# SCH_Power_Jack.net
KiCad netlist of a schematic drawn in Altium Designer
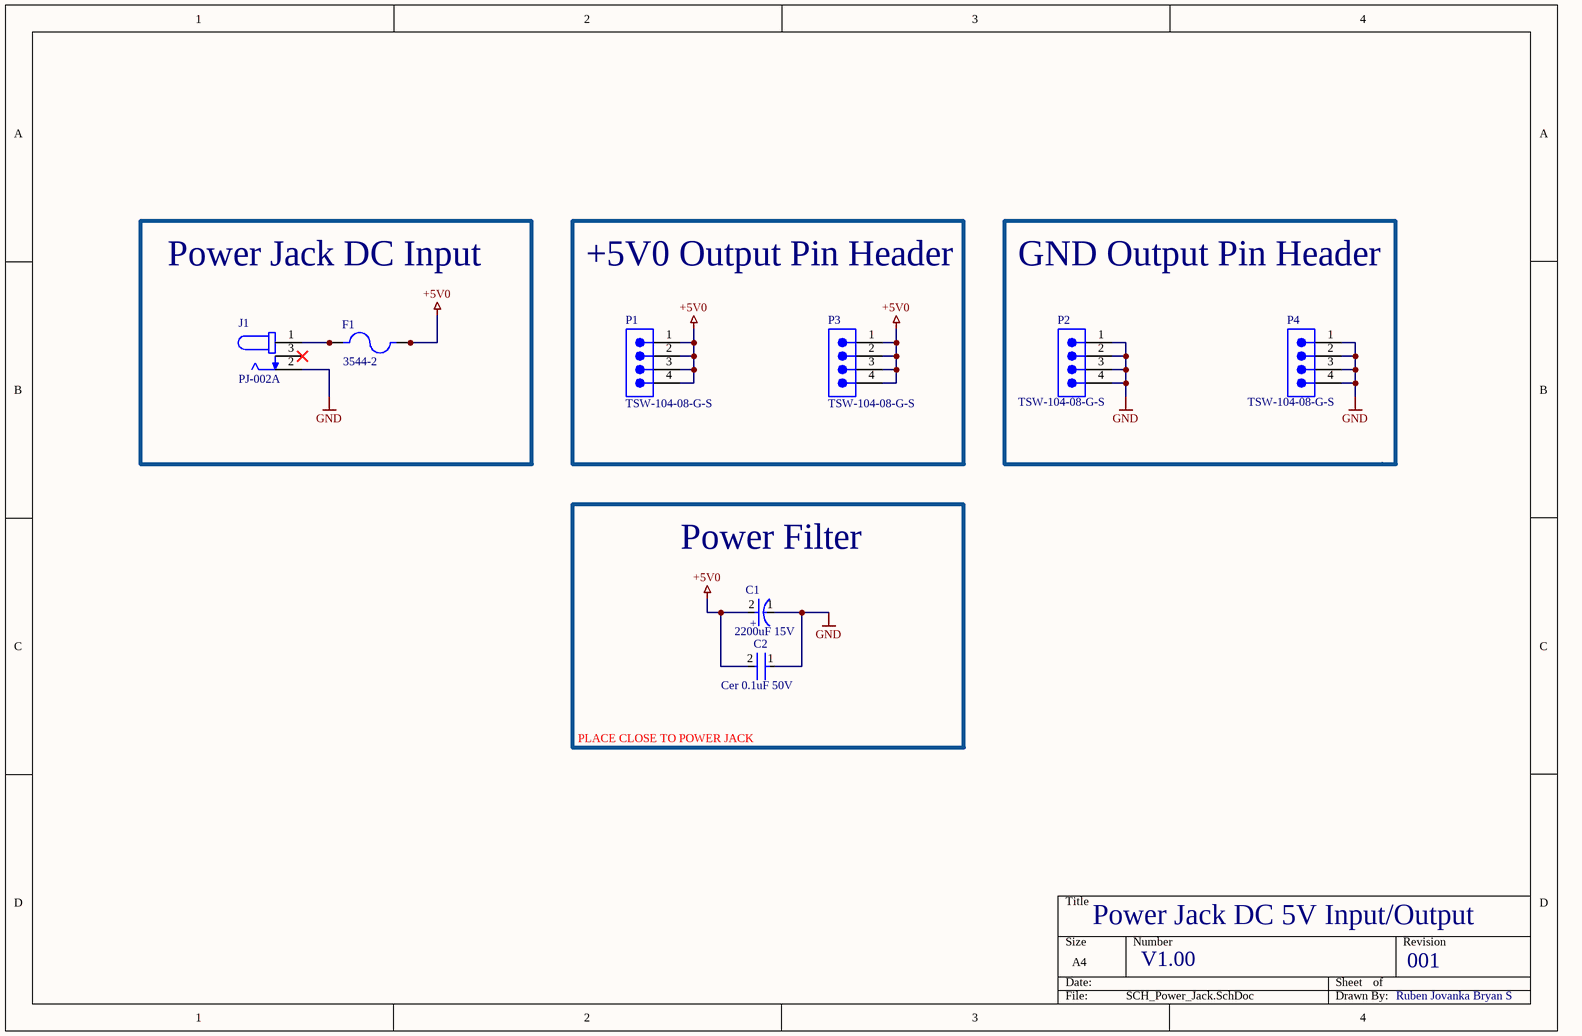
[diagram p0: SCH_Power_Jack.SchDoc]

(export (version "E")
  (design (tool "Eeschema 10.0.6"))
  (components
    (comp (ref "C1")
      (value "2200uF 15V")
      (footprint "FP-RAD-TH-D_18_0_5-L_25_2-MFG")
      (description "Aluminum Electrolytic Capacitors (Radial Lead Type) AEC-Q200 Qualified 3300uF ±20% 35V")
      (fields (field (name "VOLTAGE") "35V") (field (name "TOLERANCE") "20%"))
      (libsource (lib "Altium Content Vault") (part "a00bbbee19879c290e62620ae7e47b1"))
    )
    (comp (ref "C2")
      (value "Cer 0.1uF 50V")
      (footprint "FP-K15H5-MFG")
      (description "CAP CER 0.1UF 50V X7R RADIAL")
      (fields (field (name "TOLERANCE") "10%") (field (name "VOLTAGE") "50V"))
      (libsource (lib "Altium Content Vault") (part "02cd4be3c70576c341d710602a673aa"))
    )
    (comp (ref "F1")
      (value "3544-2")
      (footprint "FUSE_3544-2")
      (fields (field (name "MF") "Keystone Electronics"))
      (libsource (lib "3544-2") (part "3544-2"))
    )
    (comp (ref "J1")
      (value "PJ-002A")
      (footprint "CUI_PJ-002A")
      (description "2.0 x 6.5 mm, 2.5 A, Horizontal, Through Hole, Dc Power Jack Connector")
      (fields (field (name "MF") "Same Sky"))
      (libsource (lib "PJ-002A") (part "PJ-002A"))
    )
    (comp (ref "P1")
      (value "TSW-104-08-G-S")
      (footprint "SMTC-TSW-104-08-X-S")
      (description "0.025\" SQ Post Header, Through-hole, Vertical, -55 to 125 degC, 2.54 mm Pitch, 4-Pin, Male, RoHS")
      (fields (field (name "MANUFACTURER") "Samtec"))
      (libsource (lib "Altium Content Vault") (part "SMTC-TSW-104-08-X-S"))
    )
    (comp (ref "P2")
      (value "TSW-104-08-G-S")
      (footprint "SMTC-TSW-104-08-X-S")
      (description "0.025\" SQ Post Header, Through-hole, Vertical, -55 to 125 degC, 2.54 mm Pitch, 4-Pin, Male, RoHS")
      (fields (field (name "MANUFACTURER") "Samtec"))
      (libsource (lib "Altium Content Vault") (part "SMTC-TSW-104-08-X-S"))
    )
    (comp (ref "P3")
      (value "TSW-104-08-G-S")
      (footprint "SMTC-TSW-104-08-X-S")
      (description "0.025\" SQ Post Header, Through-hole, Vertical, -55 to 125 degC, 2.54 mm Pitch, 4-Pin, Male, RoHS")
      (fields (field (name "MANUFACTURER") "Samtec"))
      (libsource (lib "Altium Content Vault") (part "SMTC-TSW-104-08-X-S"))
    )
    (comp (ref "P4")
      (value "TSW-104-08-G-S")
      (footprint "SMTC-TSW-104-08-X-S")
      (description "0.025\" SQ Post Header, Through-hole, Vertical, -55 to 125 degC, 2.54 mm Pitch, 4-Pin, Male, RoHS")
      (fields (field (name "MANUFACTURER") "Samtec"))
      (libsource (lib "Altium Content Vault") (part "SMTC-TSW-104-08-X-S"))
    )
  )
  (nets
    (net (code "1") (name "+5V0") (class "Default")
      (node (ref "C1") (pin "2") (pinfunction "A_2") (pintype "passive"))
      (node (ref "C2") (pin "2") (pinfunction "2_2") (pintype "passive"))
      (node (ref "F1") (pin "2_1") (pinfunction "2_2_1") (pintype "passive"))
      (node (ref "F1") (pin "2_2") (pinfunction "2_2_2") (pintype "passive"))
      (node (ref "P1") (pin "1") (pinfunction "1_1") (pintype "passive"))
      (node (ref "P1") (pin "2") (pinfunction "2_2") (pintype "passive"))
      (node (ref "P1") (pin "3") (pinfunction "3_3") (pintype "passive"))
      (node (ref "P1") (pin "4") (pinfunction "4_4") (pintype "passive"))
      (node (ref "P3") (pin "1") (pinfunction "1_1") (pintype "passive"))
      (node (ref "P3") (pin "2") (pinfunction "2_2") (pintype "passive"))
      (node (ref "P3") (pin "3") (pinfunction "3_3") (pintype "passive"))
      (node (ref "P3") (pin "4") (pinfunction "4_4") (pintype "passive"))
    )
    (net (code "2") (name "GND") (class "Default")
      (node (ref "C1") (pin "1") (pinfunction "C_1") (pintype "passive"))
      (node (ref "C2") (pin "1") (pinfunction "1_1") (pintype "passive"))
      (node (ref "J1") (pin "2") (pinfunction "2_2") (pintype "passive"))
      (node (ref "P2") (pin "1") (pinfunction "1_1") (pintype "passive"))
      (node (ref "P2") (pin "2") (pinfunction "2_2") (pintype "passive"))
      (node (ref "P2") (pin "3") (pinfunction "3_3") (pintype "passive"))
      (node (ref "P2") (pin "4") (pinfunction "4_4") (pintype "passive"))
      (node (ref "P4") (pin "1") (pinfunction "1_1") (pintype "passive"))
      (node (ref "P4") (pin "2") (pinfunction "2_2") (pintype "passive"))
      (node (ref "P4") (pin "3") (pinfunction "3_3") (pintype "passive"))
      (node (ref "P4") (pin "4") (pinfunction "4_4") (pintype "passive"))
    )
    (net (code "3") (name "Net-(F1-1-Pad1_1)") (class "Default")
      (node (ref "F1") (pin "1_1") (pinfunction "1_1_1") (pintype "passive"))
      (node (ref "F1") (pin "1_2") (pinfunction "1_1_2") (pintype "passive"))
      (node (ref "J1") (pin "1") (pinfunction "1_1") (pintype "passive"))
    )
    (net (code "4") (name "unconnected-(J1-Pad3)") (class "Default")
      (node (ref "J1") (pin "3") (pinfunction "3_3") (pintype "passive+no_connect"))
    )
  )
)
